# TouScruino-avr-v0.net
KiCad netlist of a schematic drawn in EAGLE
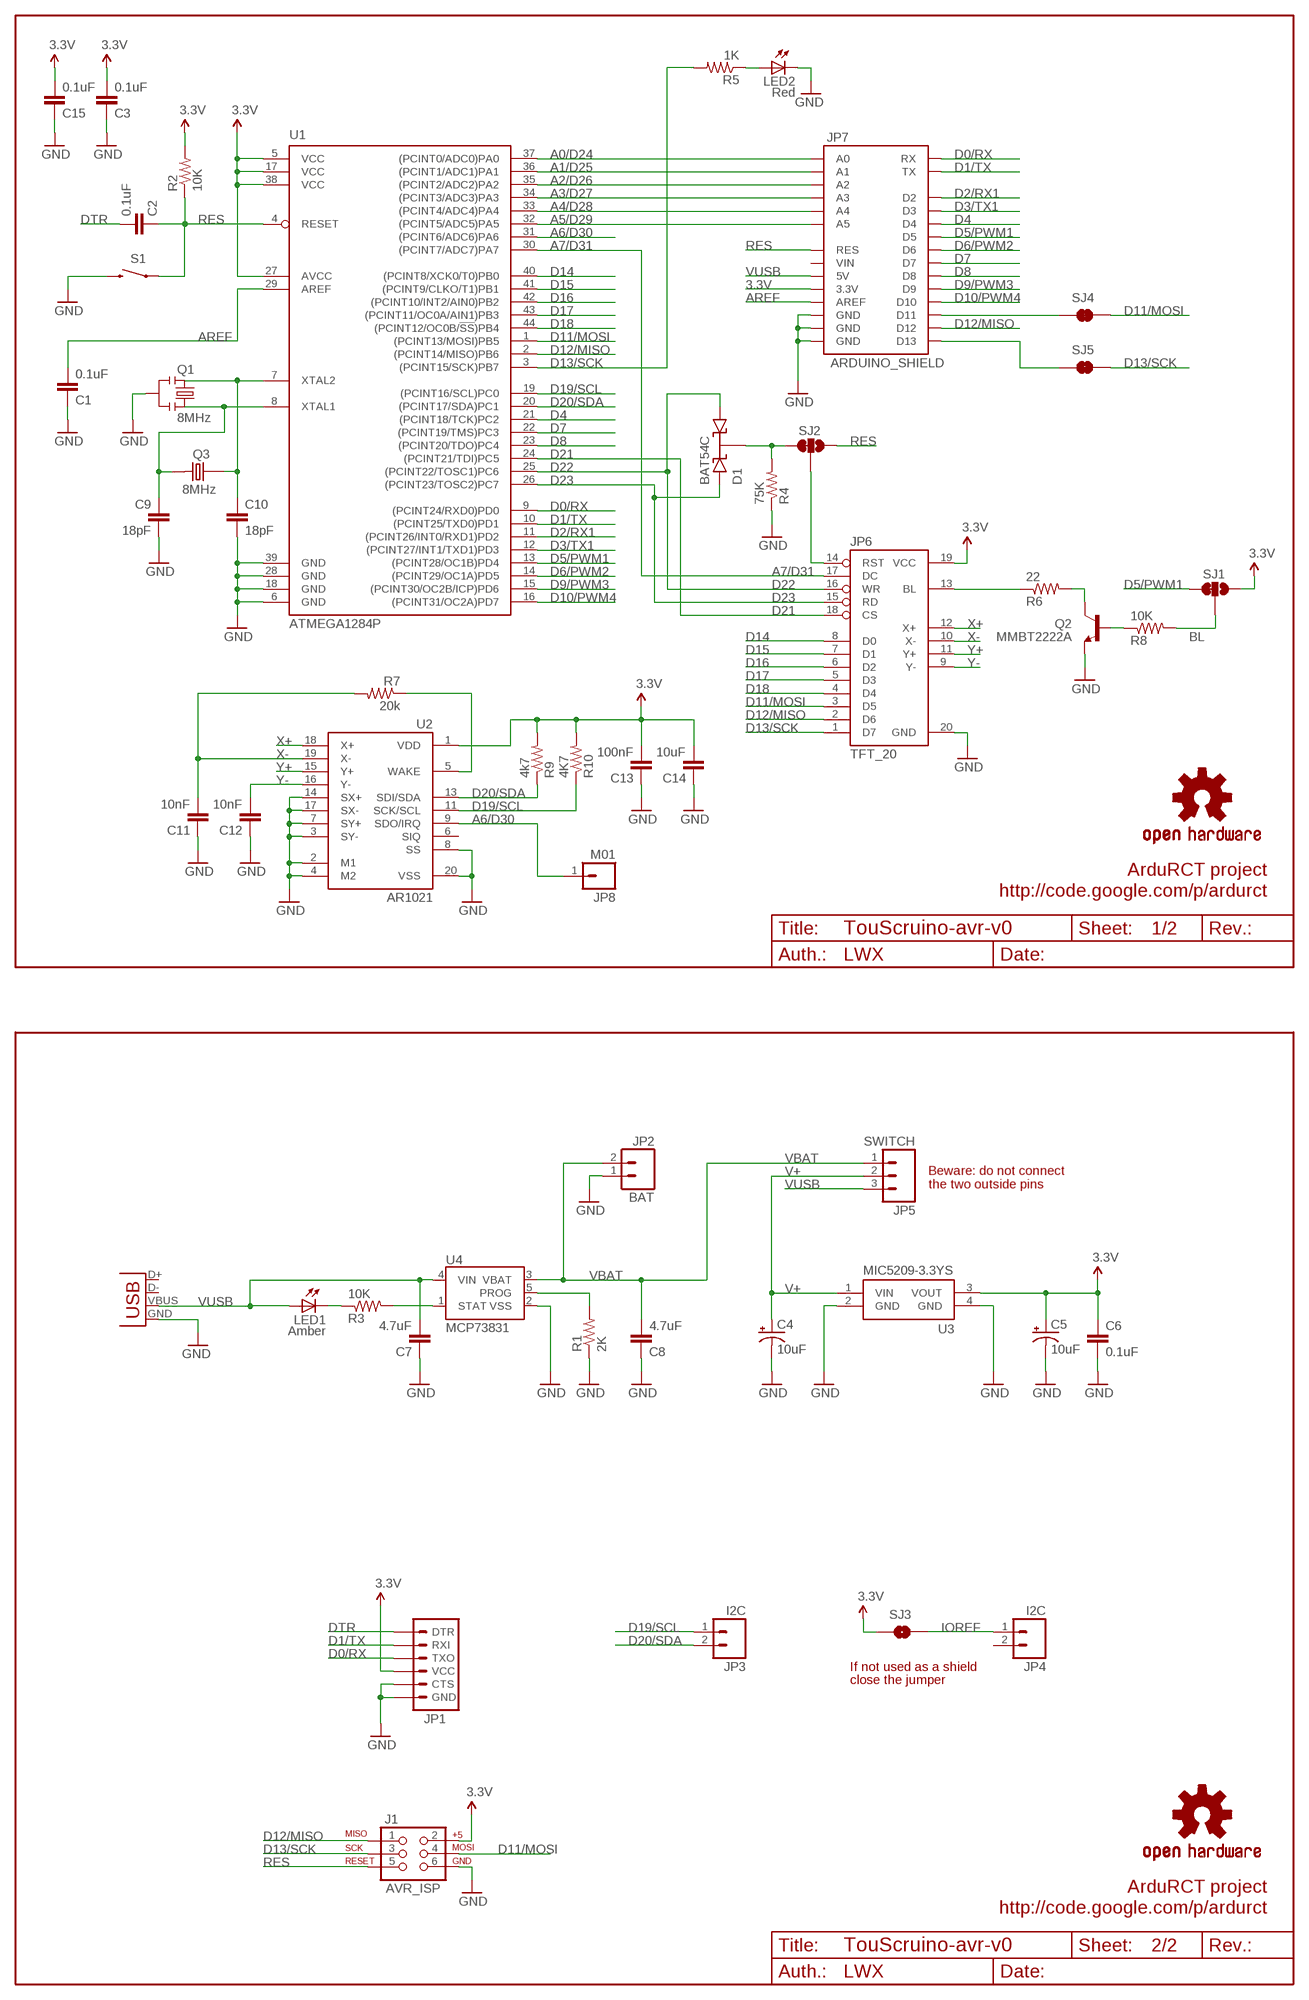
[diagram p0: schematic, sheet 1]

(export (version "E")
  (design (tool "Eeschema 10.0.6"))
  (components
    (comp (ref "C1")
      (value "0.1uF")
      (footprint "eagle-import:0805")
      (libsource (lib "eagle-import") (part "CAP0805"))
    )
    (comp (ref "C2")
      (value "0.1uF")
      (footprint "eagle-import:0805")
      (libsource (lib "eagle-import") (part "CAP0805"))
    )
    (comp (ref "C3")
      (value "0.1uF")
      (footprint "eagle-import:0805")
      (libsource (lib "eagle-import") (part "CAP0805"))
    )
    (comp (ref "C4")
      (value "10uF")
      (footprint "eagle-import:EIA3216")
      (libsource (lib "eagle-import") (part "CAP_POL1206"))
    )
    (comp (ref "C5")
      (value "10uF")
      (footprint "eagle-import:EIA3216")
      (libsource (lib "eagle-import") (part "CAP_POL1206"))
    )
    (comp (ref "C6")
      (value "0.1uF")
      (footprint "eagle-import:0805")
      (libsource (lib "eagle-import") (part "CAP0805"))
    )
    (comp (ref "C7")
      (value "4.7uF")
      (footprint "eagle-import:0805")
      (libsource (lib "eagle-import") (part "CAP0805"))
    )
    (comp (ref "C8")
      (value "4.7uF")
      (footprint "eagle-import:0805")
      (libsource (lib "eagle-import") (part "CAP0805"))
    )
    (comp (ref "C9")
      (value "18pF")
      (footprint "eagle-import:0603-CAP")
      (libsource (lib "eagle-import") (part "CAP0603-CAP"))
    )
    (comp (ref "C10")
      (value "18pF")
      (footprint "eagle-import:0603-CAP")
      (libsource (lib "eagle-import") (part "CAP0603-CAP"))
    )
    (comp (ref "C11")
      (value "10nF")
      (footprint "eagle-import:0805")
      (libsource (lib "eagle-import") (part "CAP0805"))
    )
    (comp (ref "C12")
      (value "10nF")
      (footprint "eagle-import:0805")
      (libsource (lib "eagle-import") (part "CAP0805"))
    )
    (comp (ref "C13")
      (value "100nF")
      (footprint "eagle-import:0805")
      (libsource (lib "eagle-import") (part "CAP0805"))
    )
    (comp (ref "C14")
      (value "10uF")
      (footprint "eagle-import:0805")
      (libsource (lib "eagle-import") (part "CAP0805"))
    )
    (comp (ref "C15")
      (value "0.1uF")
      (footprint "eagle-import:0805")
      (libsource (lib "eagle-import") (part "CAP0805"))
    )
    (comp (ref "D1")
      (value "BAT54C")
      (footprint "eagle-import:SOT23-3")
      (libsource (lib "eagle-import") (part "BAT54C"))
    )
    (comp (ref "J1")
      (value "AVR_ISP")
      (footprint "eagle-import:2X3")
      (libsource (lib "eagle-import") (part "AVR_SPI_PRG_6PTH"))
    )
    (comp (ref "JP1")
      (value "ARDUINO_SERIAL_PROGRAMPTH")
      (footprint "eagle-import:1X06")
      (libsource (lib "eagle-import") (part "ARDUINO_SERIAL_PROGRAMPTH"))
    )
    (comp (ref "JP2")
      (value "BAT")
      (footprint "eagle-import:JST-2-SMD")
      (libsource (lib "eagle-import") (part "M02-JST-2MM-SMT"))
    )
    (comp (ref "JP3")
      (value "I2C")
      (footprint "eagle-import:1X02")
      (libsource (lib "eagle-import") (part "M02"))
    )
    (comp (ref "JP4")
      (value "I2C")
      (footprint "eagle-import:1X02")
      (libsource (lib "eagle-import") (part "M02"))
    )
    (comp (ref "JP5")
      (value "SWITCH")
      (footprint "eagle-import:1X3_LONGPAD")
      (libsource (lib "eagle-import") (part "M03"))
    )
    (comp (ref "JP6")
      (value "TFT_20")
      (footprint "eagle-import:TFT_20")
      (libsource (lib "eagle-import") (part "TFT_20"))
    )
    (comp (ref "JP7")
      (value "ARDUINO_SHIELD")
      (footprint "eagle-import:ARDUINO_SHIELD")
      (libsource (lib "eagle-import") (part "ARDUINO_SHIELD"))
    )
    (comp (ref "JP8")
      (value "M01")
      (footprint "eagle-import:1X1")
      (libsource (lib "eagle-import") (part "M01"))
    )
    (comp (ref "LED1")
      (value "Amber")
      (footprint "eagle-import:LED")
      (libsource (lib "eagle-import") (part "LED"))
    )
    (comp (ref "LED2")
      (value "Red")
      (footprint "eagle-import:LED")
      (libsource (lib "eagle-import") (part "LED"))
    )
    (comp (ref "Q1")
      (value "8MHz")
      (footprint "eagle-import:RESONATOR-SMD")
      (libsource (lib "eagle-import") (part "RESONATORSMD"))
    )
    (comp (ref "Q2")
      (value "MMBT2222A")
      (footprint "eagle-import:SOT23-3")
      (libsource (lib "eagle-import") (part "TRANSISTOR_NPNSOT23-3"))
    )
    (comp (ref "Q3")
      (value "8MHz")
      (footprint "eagle-import:CRYSTAL_5X3.2")
      (libsource (lib "eagle-import") (part "CRYSTAL_5X3.2"))
    )
    (comp (ref "R1")
      (value "2K")
      (footprint "eagle-import:0805")
      (libsource (lib "eagle-import") (part "RESISTOR0805-RES"))
    )
    (comp (ref "R2")
      (value "10K")
      (footprint "eagle-import:0805")
      (libsource (lib "eagle-import") (part "RESISTOR0805-RES"))
    )
    (comp (ref "R3")
      (value "10K")
      (footprint "eagle-import:0805")
      (libsource (lib "eagle-import") (part "RESISTOR0805-RES"))
    )
    (comp (ref "R4")
      (value "75K")
      (footprint "eagle-import:0805")
      (libsource (lib "eagle-import") (part "RESISTOR0805-RES"))
    )
    (comp (ref "R5")
      (value "1K")
      (footprint "eagle-import:0805")
      (libsource (lib "eagle-import") (part "RESISTOR0805-RES"))
    )
    (comp (ref "R6")
      (value "22")
      (footprint "eagle-import:0805")
      (libsource (lib "eagle-import") (part "RESISTOR0805-RES"))
    )
    (comp (ref "R7")
      (value "20k")
      (footprint "eagle-import:0805")
      (libsource (lib "eagle-import") (part "RESISTOR0805-RES"))
    )
    (comp (ref "R8")
      (value "10K")
      (footprint "eagle-import:0805")
      (libsource (lib "eagle-import") (part "RESISTOR0805-RES"))
    )
    (comp (ref "R9")
      (value "4k7")
      (footprint "eagle-import:0805")
      (libsource (lib "eagle-import") (part "RESISTOR0805-RES"))
    )
    (comp (ref "R10")
      (value "4K7")
      (footprint "eagle-import:0805")
      (libsource (lib "eagle-import") (part "RESISTOR0805-RES"))
    )
    (comp (ref "S1")
      (value "SWITCH-MOMENTARY-2SMD")
      (footprint "eagle-import:TACTILE_SWITCH_SMD")
      (libsource (lib "eagle-import") (part "SWITCH-MOMENTARY-2SMD"))
    )
    (comp (ref "SJ1")
      (value "SJ_2WAYS_1-2")
      (footprint "eagle-import:SJ_2WAYS_1-2_S")
      (libsource (lib "eagle-import") (part "SJ_2WAYS_1-2"))
    )
    (comp (ref "SJ2")
      (value "SJ_2WAYS_1-2")
      (footprint "eagle-import:SJ_2WAYS_1-2_S")
      (libsource (lib "eagle-import") (part "SJ_2WAYS_1-2"))
    )
    (comp (ref "SJ3")
      (value "SOLDERJUMPERNO")
      (footprint "eagle-import:SJ_2S-NO")
      (libsource (lib "eagle-import") (part "SOLDERJUMPERNO"))
    )
    (comp (ref "SJ4")
      (value "SOLDERJUMPERTRACE")
      (footprint "eagle-import:SJ_2S-TRACE")
      (libsource (lib "eagle-import") (part "SOLDERJUMPERTRACE"))
    )
    (comp (ref "SJ5")
      (value "SOLDERJUMPERTRACE")
      (footprint "eagle-import:SJ_2S-TRACE")
      (libsource (lib "eagle-import") (part "SOLDERJUMPERTRACE"))
    )
    (comp (ref "U$3")
      (value "OSHW-LOGOM")
      (footprint "eagle-import:OSHW-LOGO-M")
      (libsource (lib "eagle-import") (part "OSHW-LOGOM"))
    )
    (comp (ref "U$5")
      (value "OSHW-LOGOM")
      (footprint "eagle-import:OSHW-LOGO-M")
      (libsource (lib "eagle-import") (part "OSHW-LOGOM"))
    )
    (comp (ref "U1")
      (value "ATMEGA1284P")
      (footprint "eagle-import:TQFP44")
      (libsource (lib "eagle-import") (part "ATMEGA324A"))
    )
    (comp (ref "U2")
      (value "AR1021")
      (footprint "eagle-import:SSOP20")
      (libsource (lib "eagle-import") (part "AR1020"))
    )
    (comp (ref "U3")
      (value "MIC5209-3.3YS")
      (footprint "eagle-import:SOT223")
      (libsource (lib "eagle-import") (part "MIC5209"))
    )
    (comp (ref "U4")
      (value "MCP73831")
      (footprint "eagle-import:SOT23-5")
      (libsource (lib "eagle-import") (part "MCP73831"))
    )
    (comp (ref "X2")
      (value "USB-MICROB")
      (footprint "eagle-import:USB-MICROB")
      (libsource (lib "eagle-import") (part "USB-MICROB"))
    )
  )
  (nets
    (net (code "1") (name "/A0{slash}D24") (class "Default")
      (node (ref "JP7") (pin "A0") (pinfunction "A0_A0") (pintype "bidirectional"))
      (node (ref "U1") (pin "37") (pinfunction "(PCINT0/ADC0)PA0_37") (pintype "bidirectional"))
    )
    (net (code "2") (name "/A1{slash}D25") (class "Default")
      (node (ref "JP7") (pin "A1") (pinfunction "A1_A1") (pintype "bidirectional"))
      (node (ref "U1") (pin "36") (pinfunction "(PCINT1/ADC1)PA1_36") (pintype "bidirectional"))
    )
    (net (code "3") (name "/A2{slash}D26") (class "Default")
      (node (ref "JP7") (pin "A2") (pinfunction "A2_A2") (pintype "bidirectional"))
      (node (ref "U1") (pin "35") (pinfunction "(PCINT2/ADC2)PA2_35") (pintype "bidirectional"))
    )
    (net (code "4") (name "/A3{slash}D27") (class "Default")
      (node (ref "JP7") (pin "A3") (pinfunction "A3_A3") (pintype "bidirectional"))
      (node (ref "U1") (pin "34") (pinfunction "(PCINT3/ADC3)PA3_34") (pintype "bidirectional"))
    )
    (net (code "5") (name "/A4{slash}D28") (class "Default")
      (node (ref "JP7") (pin "A4") (pinfunction "A4_A4") (pintype "bidirectional"))
      (node (ref "U1") (pin "33") (pinfunction "(PCINT4/ADC4)PA4_33") (pintype "bidirectional"))
    )
    (net (code "6") (name "/A5{slash}D29") (class "Default")
      (node (ref "JP7") (pin "A5") (pinfunction "A5_A5") (pintype "bidirectional"))
      (node (ref "U1") (pin "32") (pinfunction "(PCINT5/ADC5)PA5_32") (pintype "bidirectional"))
    )
    (net (code "7") (name "/A6{slash}D30") (class "Default")
      (node (ref "JP8") (pin "1") (pinfunction "1_1") (pintype "passive"))
      (node (ref "U1") (pin "31") (pinfunction "(PCINT6/ADC6)PA6_31") (pintype "bidirectional"))
      (node (ref "U2") (pin "9") (pinfunction "SDO/IRQ_9") (pintype "bidirectional"))
    )
    (net (code "8") (name "/A7{slash}D31") (class "Default")
      (node (ref "JP6") (pin "17") (pinfunction "DC_17") (pintype "bidirectional"))
      (node (ref "U1") (pin "30") (pinfunction "(PCINT7/ADC7)PA7_30") (pintype "bidirectional"))
    )
    (net (code "9") (name "/AREF") (class "Default")
      (node (ref "C1") (pin "2") (pinfunction "2_2") (pintype "passive"))
      (node (ref "JP7") (pin "AREF") (pinfunction "AREF_AREF") (pintype "bidirectional"))
      (node (ref "U1") (pin "29") (pinfunction "AREF_29") (pintype "passive"))
    )
    (net (code "10") (name "/BL") (class "Default")
      (node (ref "R8") (pin "2") (pinfunction "2_2") (pintype "passive"))
      (node (ref "SJ1") (pin "2") (pinfunction "2_2") (pintype "passive"))
    )
    (net (code "11") (name "/D0{slash}RX") (class "Default")
      (node (ref "JP1") (pin "3") (pinfunction "TXO_3") (pintype "passive"))
      (node (ref "JP7") (pin "RX") (pinfunction "RX_RX") (pintype "bidirectional"))
      (node (ref "U1") (pin "9") (pinfunction "(PCINT24/RXD0)PD0_9") (pintype "bidirectional"))
    )
    (net (code "12") (name "/D1{slash}TX") (class "Default")
      (node (ref "JP1") (pin "2") (pinfunction "RXI_2") (pintype "passive"))
      (node (ref "JP7") (pin "TX") (pinfunction "TX_TX") (pintype "bidirectional"))
      (node (ref "U1") (pin "10") (pinfunction "(PCINT25/TXD0)PD1_10") (pintype "bidirectional"))
    )
    (net (code "13") (name "/D2{slash}RX1") (class "Default")
      (node (ref "JP7") (pin "D2") (pinfunction "D2_D2") (pintype "bidirectional"))
      (node (ref "U1") (pin "11") (pinfunction "(PCINT26/INT0/RXD1)PD2_11") (pintype "bidirectional"))
    )
    (net (code "14") (name "/D3{slash}TX1") (class "Default")
      (node (ref "JP7") (pin "D3") (pinfunction "D3_D3") (pintype "bidirectional"))
      (node (ref "U1") (pin "12") (pinfunction "(PCINT27/INT1/TXD1)PD3_12") (pintype "bidirectional"))
    )
    (net (code "15") (name "/D4") (class "Default")
      (node (ref "JP7") (pin "D4") (pinfunction "D4_D4") (pintype "bidirectional"))
      (node (ref "U1") (pin "21") (pinfunction "(PCINT18/TCK)PC2_21") (pintype "output"))
    )
    (net (code "16") (name "/D5{slash}PWM1") (class "Default")
      (node (ref "JP7") (pin "D5") (pinfunction "D5_D5") (pintype "bidirectional"))
      (node (ref "SJ1") (pin "1") (pinfunction "1_1") (pintype "passive"))
      (node (ref "U1") (pin "13") (pinfunction "(PCINT28/OC1B)PD4_13") (pintype "bidirectional"))
    )
    (net (code "17") (name "/D6{slash}PWM2") (class "Default")
      (node (ref "JP7") (pin "D6") (pinfunction "D6_D6") (pintype "bidirectional"))
      (node (ref "U1") (pin "14") (pinfunction "(PCINT29/OC1A)PD5_14") (pintype "bidirectional"))
    )
    (net (code "18") (name "/D7") (class "Default")
      (node (ref "JP7") (pin "D7") (pinfunction "D7_D7") (pintype "bidirectional"))
      (node (ref "U1") (pin "22") (pinfunction "(PCINT19/TMS)PC3_22") (pintype "output"))
    )
    (net (code "19") (name "/D8") (class "Default")
      (node (ref "JP7") (pin "D8") (pinfunction "D8_D8") (pintype "bidirectional"))
      (node (ref "U1") (pin "23") (pinfunction "(PCINT20/TDO)PC4_23") (pintype "output"))
    )
    (net (code "20") (name "/D9{slash}PWM3") (class "Default")
      (node (ref "JP7") (pin "D9") (pinfunction "D9_D9") (pintype "bidirectional"))
      (node (ref "U1") (pin "15") (pinfunction "(PCINT30/OC2B/ICP)PD6_15") (pintype "bidirectional"))
    )
    (net (code "21") (name "/D10{slash}PWM4") (class "Default")
      (node (ref "JP7") (pin "D10") (pinfunction "D10_D10") (pintype "bidirectional"))
      (node (ref "U1") (pin "16") (pinfunction "(PCINT31/OC2A)PD7_16") (pintype "bidirectional"))
    )
    (net (code "22") (name "/D11{slash}MOSI") (class "Default")
      (node (ref "J1") (pin "4") (pinfunction "4_4") (pintype "passive"))
      (node (ref "JP6") (pin "3") (pinfunction "D5_3") (pintype "bidirectional"))
      (node (ref "SJ4") (pin "2") (pinfunction "2_2") (pintype "passive"))
      (node (ref "U1") (pin "1") (pinfunction "(PCINT13/MOSI)PB5_1") (pintype "bidirectional"))
    )
    (net (code "23") (name "/D12{slash}MISO") (class "Default")
      (node (ref "J1") (pin "1") (pinfunction "1_1") (pintype "passive"))
      (node (ref "JP6") (pin "2") (pinfunction "D6_2") (pintype "bidirectional"))
      (node (ref "JP7") (pin "D12") (pinfunction "D12_D12") (pintype "bidirectional"))
      (node (ref "U1") (pin "2") (pinfunction "(PCINT14/MISO)PB6_2") (pintype "bidirectional"))
    )
    (net (code "24") (name "/D13{slash}SCK") (class "Default")
      (node (ref "J1") (pin "3") (pinfunction "3_3") (pintype "passive"))
      (node (ref "JP6") (pin "1") (pinfunction "D7_1") (pintype "bidirectional"))
      (node (ref "R5") (pin "2") (pinfunction "2_2") (pintype "passive"))
      (node (ref "SJ5") (pin "2") (pinfunction "2_2") (pintype "passive"))
      (node (ref "U1") (pin "3") (pinfunction "(PCINT15/SCK)PB7_3") (pintype "bidirectional"))
    )
    (net (code "25") (name "/D14") (class "Default")
      (node (ref "JP6") (pin "8") (pinfunction "D0_8") (pintype "bidirectional"))
      (node (ref "U1") (pin "40") (pinfunction "(PCINT8/XCK0/T0)PB0_40") (pintype "bidirectional"))
    )
    (net (code "26") (name "/D15") (class "Default")
      (node (ref "JP6") (pin "7") (pinfunction "D1_7") (pintype "bidirectional"))
      (node (ref "U1") (pin "41") (pinfunction "(PCINT9/CLKO/T1)PB1_41") (pintype "bidirectional"))
    )
    (net (code "27") (name "/D16") (class "Default")
      (node (ref "JP6") (pin "6") (pinfunction "D2_6") (pintype "bidirectional"))
      (node (ref "U1") (pin "42") (pinfunction "(PCINT10/INT2/AIN0)PB2_42") (pintype "bidirectional"))
    )
    (net (code "28") (name "/D17") (class "Default")
      (node (ref "JP6") (pin "5") (pinfunction "D3_5") (pintype "bidirectional"))
      (node (ref "U1") (pin "43") (pinfunction "(PCINT11/OC0A/AIN1)PB3_43") (pintype "bidirectional"))
    )
    (net (code "29") (name "/D18") (class "Default")
      (node (ref "JP6") (pin "4") (pinfunction "D4_4") (pintype "bidirectional"))
      (node (ref "U1") (pin "44") (pinfunction "(PCINT12/OC0B/~{SS})PB4_44") (pintype "bidirectional"))
    )
    (net (code "30") (name "/D19{slash}SCL") (class "Default")
      (node (ref "JP3") (pin "1") (pinfunction "1_1") (pintype "passive"))
      (node (ref "R10") (pin "1") (pinfunction "1_1") (pintype "passive"))
      (node (ref "U1") (pin "19") (pinfunction "(PCINT16/SCL)PC0_19") (pintype "output"))
      (node (ref "U2") (pin "11") (pinfunction "SCK/SCL_11") (pintype "bidirectional"))
    )
    (net (code "31") (name "/D20{slash}SDA") (class "Default")
      (node (ref "JP3") (pin "2") (pinfunction "2_2") (pintype "passive"))
      (node (ref "R9") (pin "1") (pinfunction "1_1") (pintype "passive"))
      (node (ref "U1") (pin "20") (pinfunction "(PCINT17/SDA)PC1_20") (pintype "output"))
      (node (ref "U2") (pin "13") (pinfunction "SDI/SDA_13") (pintype "bidirectional"))
    )
    (net (code "32") (name "/D21") (class "Default")
      (node (ref "JP6") (pin "18") (pinfunction "CS_18") (pintype "bidirectional"))
      (node (ref "U1") (pin "24") (pinfunction "(PCINT21/TDI)PC5_24") (pintype "output"))
    )
    (net (code "33") (name "/D22") (class "Default")
      (node (ref "D1") (pin "1") (pinfunction "A1_1") (pintype "bidirectional"))
      (node (ref "JP6") (pin "16") (pinfunction "WR_16") (pintype "bidirectional"))
      (node (ref "U1") (pin "25") (pinfunction "(PCINT22/TOSC1)PC6_25") (pintype "output"))
    )
    (net (code "34") (name "/D23") (class "Default")
      (node (ref "D1") (pin "2") (pinfunction "A2_2") (pintype "bidirectional"))
      (node (ref "JP6") (pin "15") (pinfunction "RD_15") (pintype "bidirectional"))
      (node (ref "U1") (pin "26") (pinfunction "(PCINT23/TOSC2)PC7_26") (pintype "output"))
    )
    (net (code "35") (name "/DTR") (class "Default")
      (node (ref "C2") (pin "2") (pinfunction "2_2") (pintype "passive"))
      (node (ref "JP1") (pin "1") (pinfunction "DTR_1") (pintype "passive"))
    )
    (net (code "36") (name "/IOREF") (class "Default")
      (node (ref "JP4") (pin "1") (pinfunction "1_1") (pintype "passive"))
      (node (ref "SJ3") (pin "2") (pinfunction "2_2") (pintype "passive"))
    )
    (net (code "37") (name "/RES") (class "Default")
      (node (ref "C2") (pin "1") (pinfunction "1_1") (pintype "passive"))
      (node (ref "J1") (pin "5") (pinfunction "5_5") (pintype "passive"))
      (node (ref "JP7") (pin "RES") (pinfunction "RES_RES") (pintype "bidirectional"))
      (node (ref "R2") (pin "1") (pinfunction "1_1") (pintype "passive"))
      (node (ref "S1") (pin "1") (pinfunction "1_1") (pintype "passive"))
      (node (ref "SJ2") (pin "3") (pinfunction "3_3") (pintype "passive"))
      (node (ref "U1") (pin "4") (pinfunction "RESET_4") (pintype "input"))
    )
    (net (code "38") (name "/V+") (class "Default")
      (node (ref "C4") (pin "A") (pinfunction "+_A") (pintype "passive"))
      (node (ref "JP5") (pin "2") (pinfunction "2_2") (pintype "passive"))
      (node (ref "U3") (pin "1") (pinfunction "VIN_1") (pintype "bidirectional"))
    )
    (net (code "39") (name "/VBAT") (class "Default")
      (node (ref "C8") (pin "2") (pinfunction "2_2") (pintype "passive"))
      (node (ref "JP2") (pin "2") (pinfunction "2_2") (pintype "passive"))
      (node (ref "JP5") (pin "1") (pinfunction "1_1") (pintype "passive"))
      (node (ref "U4") (pin "3") (pinfunction "VBAT_3") (pintype "power_in"))
    )
    (net (code "40") (name "/VUSB") (class "Default")
      (node (ref "C7") (pin "2") (pinfunction "2_2") (pintype "passive"))
      (node (ref "JP5") (pin "3") (pinfunction "3_3") (pintype "passive"))
      (node (ref "JP7") (pin "5V") (pinfunction "5V_5V") (pintype "bidirectional"))
      (node (ref "LED1") (pin "A1") (pinfunction "A_A1") (pintype "passive"))
      (node (ref "U4") (pin "4") (pinfunction "VIN_4") (pintype "power_in"))
      (node (ref "X2") (pin "VBUS") (pinfunction "VBUS_VBUS") (pintype "bidirectional"))
    )
    (net (code "41") (name "/X+") (class "Default")
      (node (ref "JP6") (pin "12") (pinfunction "X+_12") (pintype "bidirectional"))
      (node (ref "U2") (pin "18") (pinfunction "X+_18") (pintype "bidirectional"))
    )
    (net (code "42") (name "/X-") (class "Default")
      (node (ref "C11") (pin "2") (pinfunction "2_2") (pintype "passive"))
      (node (ref "JP6") (pin "10") (pinfunction "X-_10") (pintype "bidirectional"))
      (node (ref "R7") (pin "2") (pinfunction "2_2") (pintype "passive"))
      (node (ref "U2") (pin "19") (pinfunction "X-_19") (pintype "bidirectional"))
    )
    (net (code "43") (name "/Y+") (class "Default")
      (node (ref "JP6") (pin "11") (pinfunction "Y+_11") (pintype "bidirectional"))
      (node (ref "U2") (pin "15") (pinfunction "Y+_15") (pintype "bidirectional"))
    )
    (net (code "44") (name "/Y-") (class "Default")
      (node (ref "C12") (pin "2") (pinfunction "2_2") (pintype "passive"))
      (node (ref "JP6") (pin "9") (pinfunction "Y-_9") (pintype "bidirectional"))
      (node (ref "U2") (pin "16") (pinfunction "Y-_16") (pintype "bidirectional"))
    )
    (net (code "45") (name "3.3V") (class "Default")
      (node (ref "C13") (pin "2") (pinfunction "2_2") (pintype "passive"))
      (node (ref "C14") (pin "2") (pinfunction "2_2") (pintype "passive"))
      (node (ref "C15") (pin "2") (pinfunction "2_2") (pintype "passive"))
      (node (ref "C3") (pin "2") (pinfunction "2_2") (pintype "passive"))
      (node (ref "C5") (pin "A") (pinfunction "+_A") (pintype "passive"))
      (node (ref "C6") (pin "1") (pinfunction "1_1") (pintype "passive"))
      (node (ref "J1") (pin "2") (pinfunction "2_2") (pintype "passive"))
      (node (ref "JP1") (pin "4") (pinfunction "VCC_4") (pintype "passive"))
      (node (ref "JP6") (pin "19") (pinfunction "VCC_19") (pintype "bidirectional"))
      (node (ref "JP7") (pin "3.3V") (pinfunction "3.3V_3.3V") (pintype "bidirectional"))
      (node (ref "R10") (pin "2") (pinfunction "2_2") (pintype "passive"))
      (node (ref "R2") (pin "2") (pinfunction "2_2") (pintype "passive"))
      (node (ref "R9") (pin "2") (pinfunction "2_2") (pintype "passive"))
      (node (ref "SJ1") (pin "3") (pinfunction "3_3") (pintype "passive"))
      (node (ref "SJ3") (pin "1") (pinfunction "1_1") (pintype "passive"))
      (node (ref "U1") (pin "17") (pinfunction "VCC_17") (pintype "power_in"))
      (node (ref "U1") (pin "27") (pinfunction "AVCC_27") (pintype "power_in"))
      (node (ref "U1") (pin "38") (pinfunction "VCC_38") (pintype "power_in"))
      (node (ref "U1") (pin "5") (pinfunction "VCC_5") (pintype "power_in"))
      (node (ref "U2") (pin "1") (pinfunction "VDD_1") (pintype "bidirectional"))
      (node (ref "U3") (pin "3") (pinfunction "VOUT_3") (pintype "bidirectional"))
    )
    (net (code "46") (name "GND") (class "Default")
      (node (ref "C1") (pin "1") (pinfunction "1_1") (pintype "passive"))
      (node (ref "C10") (pin "2") (pinfunction "2_2") (pintype "passive"))
      (node (ref "C11") (pin "1") (pinfunction "1_1") (pintype "passive"))
      (node (ref "C12") (pin "1") (pinfunction "1_1") (pintype "passive"))
      (node (ref "C13") (pin "1") (pinfunction "1_1") (pintype "passive"))
      (node (ref "C14") (pin "1") (pinfunction "1_1") (pintype "passive"))
      (node (ref "C15") (pin "1") (pinfunction "1_1") (pintype "passive"))
      (node (ref "C3") (pin "1") (pinfunction "1_1") (pintype "passive"))
      (node (ref "C4") (pin "C") (pinfunction "-_C") (pintype "passive"))
      (node (ref "C5") (pin "C") (pinfunction "-_C") (pintype "passive"))
      (node (ref "C6") (pin "2") (pinfunction "2_2") (pintype "passive"))
      (node (ref "C7") (pin "1") (pinfunction "1_1") (pintype "passive"))
      (node (ref "C8") (pin "1") (pinfunction "1_1") (pintype "passive"))
      (node (ref "C9") (pin "2") (pinfunction "2_2") (pintype "passive"))
      (node (ref "J1") (pin "6") (pinfunction "6_6") (pintype "passive"))
      (node (ref "JP1") (pin "5") (pinfunction "CTS_5") (pintype "passive"))
      (node (ref "JP1") (pin "6") (pinfunction "GND_6") (pintype "passive"))
      (node (ref "JP2") (pin "1") (pinfunction "1_1") (pintype "passive"))
      (node (ref "JP6") (pin "20") (pinfunction "GND_20") (pintype "bidirectional"))
      (node (ref "JP7") (pin "GND@0") (pinfunction "GND_GND@0") (pintype "bidirectional"))
      (node (ref "JP7") (pin "GND@1") (pinfunction "GND_GND@1") (pintype "bidirectional"))
      (node (ref "JP7") (pin "GND@2") (pinfunction "GND_GND@2") (pintype "bidirectional"))
      (node (ref "LED2") (pin "C1") (pinfunction "C_C1") (pintype "passive"))
      (node (ref "Q1") (pin "2") (pinfunction "2_2") (pintype "passive"))
      (node (ref "Q2") (pin "2") (pinfunction "E_2") (pintype "passive"))
      (node (ref "R1") (pin "1") (pinfunction "1_1") (pintype "passive"))
      (node (ref "R4") (pin "1") (pinfunction "1_1") (pintype "passive"))
      (node (ref "S1") (pin "3") (pinfunction "2_3") (pintype "passive"))
      (node (ref "U1") (pin "18") (pinfunction "GND_18") (pintype "power_in"))
      (node (ref "U1") (pin "28") (pinfunction "GND_28") (pintype "power_in"))
      (node (ref "U1") (pin "39") (pinfunction "GND_39") (pintype "power_in"))
      (node (ref "U1") (pin "6") (pinfunction "GND_6") (pintype "power_in"))
      (node (ref "U2") (pin "14") (pinfunction "SX+_14") (pintype "bidirectional"))
      (node (ref "U2") (pin "17") (pinfunction "SX-_17") (pintype "bidirectional"))
      (node (ref "U2") (pin "2") (pinfunction "M1_2") (pintype "bidirectional"))
      (node (ref "U2") (pin "20") (pinfunction "VSS_20") (pintype "bidirectional"))
      (node (ref "U2") (pin "3") (pinfunction "SY-_3") (pintype "bidirectional"))
      (node (ref "U2") (pin "4") (pinfunction "M2_4") (pintype "bidirectional"))
      (node (ref "U2") (pin "7") (pinfunction "SY+_7") (pintype "bidirectional"))
      (node (ref "U2") (pin "8") (pinfunction "SS_8") (pintype "bidirectional"))
      (node (ref "U3") (pin "2") (pinfunction "GND_2") (pintype "bidirectional"))
      (node (ref "U3") (pin "4") (pinfunction "GND_4") (pintype "bidirectional"))
      (node (ref "U4") (pin "2") (pinfunction "VSS_2") (pintype "power_in"))
      (node (ref "X2") (pin "GND") (pinfunction "GND_GND") (pintype "bidirectional"))
    )
    (net (code "47") (name "Net-(D1-K)") (class "Default")
      (node (ref "D1") (pin "3") (pinfunction "K_3") (pintype "bidirectional"))
      (node (ref "R4") (pin "2") (pinfunction "2_2") (pintype "passive"))
      (node (ref "SJ2") (pin "1") (pinfunction "1_1") (pintype "passive"))
    )
    (net (code "48") (name "Net-(JP6-BL)") (class "Default")
      (node (ref "JP6") (pin "13") (pinfunction "BL_13") (pintype "bidirectional"))
      (node (ref "R6") (pin "1") (pinfunction "1_1") (pintype "passive"))
    )
    (net (code "49") (name "Net-(JP6-RST)") (class "Default")
      (node (ref "JP6") (pin "14") (pinfunction "RST_14") (pintype "bidirectional"))
      (node (ref "SJ2") (pin "2") (pinfunction "2_2") (pintype "passive"))
    )
    (net (code "50") (name "Net-(JP7-PadD11)") (class "Default")
      (node (ref "JP7") (pin "D11") (pinfunction "D11_D11") (pintype "bidirectional"))
      (node (ref "SJ4") (pin "1") (pinfunction "1_1") (pintype "passive"))
    )
    (net (code "51") (name "Net-(JP7-PadD13)") (class "Default")
      (node (ref "JP7") (pin "D13") (pinfunction "D13_D13") (pintype "bidirectional"))
      (node (ref "SJ5") (pin "1") (pinfunction "1_1") (pintype "passive"))
    )
    (net (code "52") (name "Net-(LED1-C)") (class "Default")
      (node (ref "LED1") (pin "C1") (pinfunction "C_C1") (pintype "passive"))
      (node (ref "R3") (pin "1") (pinfunction "1_1") (pintype "passive"))
    )
    (net (code "53") (name "Net-(LED2-A)") (class "Default")
      (node (ref "LED2") (pin "A1") (pinfunction "A_A1") (pintype "passive"))
      (node (ref "R5") (pin "1") (pinfunction "1_1") (pintype "passive"))
    )
    (net (code "54") (name "Net-(Q2-B)") (class "Default")
      (node (ref "Q2") (pin "1") (pinfunction "B_1") (pintype "passive"))
      (node (ref "R8") (pin "1") (pinfunction "1_1") (pintype "passive"))
    )
    (net (code "55") (name "Net-(Q2-C)") (class "Default")
      (node (ref "Q2") (pin "3") (pinfunction "C_3") (pintype "passive"))
      (node (ref "R6") (pin "2") (pinfunction "2_2") (pintype "passive"))
    )
    (net (code "56") (name "Net-(U1-XTAL1)") (class "Default")
      (node (ref "C9") (pin "1") (pinfunction "1_1") (pintype "passive"))
      (node (ref "Q1") (pin "1") (pinfunction "1_1") (pintype "passive"))
      (node (ref "Q3") (pin "2") (pinfunction "2_2") (pintype "passive"))
      (node (ref "U1") (pin "8") (pinfunction "XTAL1_8") (pintype "bidirectional"))
    )
    (net (code "57") (name "Net-(U1-XTAL2)") (class "Default")
      (node (ref "C10") (pin "1") (pinfunction "1_1") (pintype "passive"))
      (node (ref "Q1") (pin "3") (pinfunction "3_3") (pintype "passive"))
      (node (ref "Q3") (pin "1") (pinfunction "1_1") (pintype "passive"))
      (node (ref "U1") (pin "7") (pinfunction "XTAL2_7") (pintype "bidirectional"))
    )
    (net (code "58") (name "Net-(U2-WAKE)") (class "Default")
      (node (ref "R7") (pin "1") (pinfunction "1_1") (pintype "passive"))
      (node (ref "U2") (pin "5") (pinfunction "WAKE_5") (pintype "bidirectional"))
    )
    (net (code "59") (name "Net-(U4-PROG)") (class "Default")
      (node (ref "R1") (pin "2") (pinfunction "2_2") (pintype "passive"))
      (node (ref "U4") (pin "5") (pinfunction "PROG_5") (pintype "input"))
    )
    (net (code "60") (name "Net-(U4-STAT)") (class "Default")
      (node (ref "R3") (pin "2") (pinfunction "2_2") (pintype "passive"))
      (node (ref "U4") (pin "1") (pinfunction "STAT_1") (pintype "output"))
    )
    (net (code "61") (name "unconnected-(JP4-Pad2)") (class "Default")
      (node (ref "JP4") (pin "2") (pinfunction "2_2") (pintype "passive"))
    )
    (net (code "62") (name "unconnected-(JP7-PadVIN)") (class "Default")
      (node (ref "JP7") (pin "VIN") (pinfunction "VIN_VIN") (pintype "bidirectional"))
    )
    (net (code "63") (name "unconnected-(U2-SIQ-Pad6)") (class "Default")
      (node (ref "U2") (pin "6") (pinfunction "SIQ_6") (pintype "bidirectional"))
    )
    (net (code "64") (name "unconnected-(X2-PadD+)") (class "Default")
      (node (ref "X2") (pin "D+") (pinfunction "D+_D+") (pintype "bidirectional"))
    )
    (net (code "65") (name "unconnected-(X2-PadD-)") (class "Default")
      (node (ref "X2") (pin "D-") (pinfunction "D-_D-") (pintype "bidirectional"))
    )
  )
)
